# Shield_Slave_2_layers.net
KiCad netlist of a schematic drawn in EAGLE
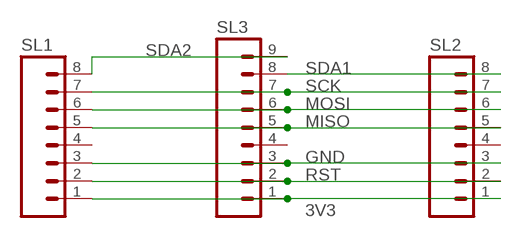
[diagram p0: schematic, sheet 1]

(export (version "E")
  (design (tool "Eeschema 10.0.6"))
  (components
    (comp (ref "SL1")
      (value "M08")
      (footprint "eagle-import:08P")
      (libsource (lib "eagle-import") (part "M08"))
    )
    (comp (ref "SL2")
      (value "M08")
      (footprint "eagle-import:08P")
      (libsource (lib "eagle-import") (part "M08"))
    )
    (comp (ref "SL3")
      (value "M09")
      (footprint "eagle-import:09P")
      (libsource (lib "eagle-import") (part "M09"))
    )
  )
  (nets
    (net (code "1") (name "/3V3") (class "Default")
      (node (ref "SL1") (pin "1") (pinfunction "1_1") (pintype "passive"))
      (node (ref "SL2") (pin "1") (pinfunction "1_1") (pintype "passive"))
      (node (ref "SL3") (pin "1") (pinfunction "1_1") (pintype "passive"))
    )
    (net (code "2") (name "/GND") (class "Default")
      (node (ref "SL1") (pin "3") (pinfunction "3_3") (pintype "passive"))
      (node (ref "SL2") (pin "3") (pinfunction "3_3") (pintype "passive"))
      (node (ref "SL3") (pin "3") (pinfunction "3_3") (pintype "passive"))
    )
    (net (code "3") (name "/MISO") (class "Default")
      (node (ref "SL1") (pin "5") (pinfunction "5_5") (pintype "passive"))
      (node (ref "SL2") (pin "5") (pinfunction "5_5") (pintype "passive"))
      (node (ref "SL3") (pin "5") (pinfunction "5_5") (pintype "passive"))
    )
    (net (code "4") (name "/MOSI") (class "Default")
      (node (ref "SL1") (pin "6") (pinfunction "6_6") (pintype "passive"))
      (node (ref "SL2") (pin "6") (pinfunction "6_6") (pintype "passive"))
      (node (ref "SL3") (pin "6") (pinfunction "6_6") (pintype "passive"))
    )
    (net (code "5") (name "/RST") (class "Default")
      (node (ref "SL1") (pin "2") (pinfunction "2_2") (pintype "passive"))
      (node (ref "SL2") (pin "2") (pinfunction "2_2") (pintype "passive"))
      (node (ref "SL3") (pin "2") (pinfunction "2_2") (pintype "passive"))
    )
    (net (code "6") (name "/SCK") (class "Default")
      (node (ref "SL1") (pin "7") (pinfunction "7_7") (pintype "passive"))
      (node (ref "SL2") (pin "7") (pinfunction "7_7") (pintype "passive"))
      (node (ref "SL3") (pin "7") (pinfunction "7_7") (pintype "passive"))
    )
    (net (code "7") (name "/SDA1") (class "Default")
      (node (ref "SL2") (pin "8") (pinfunction "8_8") (pintype "passive"))
      (node (ref "SL3") (pin "8") (pinfunction "8_8") (pintype "passive"))
    )
    (net (code "8") (name "/SDA2") (class "Default")
      (node (ref "SL1") (pin "8") (pinfunction "8_8") (pintype "passive"))
      (node (ref "SL3") (pin "9") (pinfunction "9_9") (pintype "passive"))
    )
    (net (code "9") (name "unconnected-(SL1-Pad4)") (class "Default")
      (node (ref "SL1") (pin "4") (pinfunction "4_4") (pintype "passive"))
    )
    (net (code "10") (name "unconnected-(SL2-Pad4)") (class "Default")
      (node (ref "SL2") (pin "4") (pinfunction "4_4") (pintype "passive"))
    )
    (net (code "11") (name "unconnected-(SL3-Pad4)") (class "Default")
      (node (ref "SL3") (pin "4") (pinfunction "4_4") (pintype "passive"))
    )
  )
)
